# PowerControl.net
KiCad netlist of a schematic drawn in Altium Designer
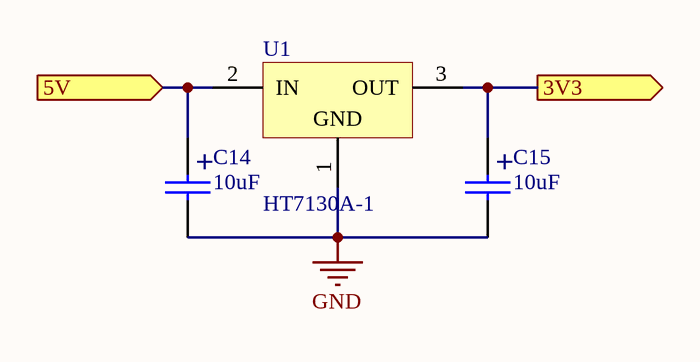
[diagram p0: PowerControl.SchDoc]

(export (version "E")
  (design (tool "Eeschema 10.0.6"))
  (components
    (comp (ref "C14") (value "10uF") (footprint "CAP100RP") (libsource (lib "LIBEBAL") (part "CAPPOL")))
    (comp (ref "C15") (value "10uF") (footprint "CAP100RP") (libsource (lib "LIBEBAL") (part "CAPPOL")))
    (comp (ref "U1")
      (value "HT7130A-1")
      (footprint "BCY-W3/E4")
      (description "3.0V 30mA Low Power,  Low Dropout Voltage (LDO) Regulator")
      (fields (field (name "PUBLISHER") "Altium Limited"))
      (libsource (lib "Holtek Power Mgt Voltage Regulator") (part "HT7130A-1"))
    )
  )
  (nets
    (net (code "1") (name "/3V3") (class "Default")
      (node (ref "C15") (pin "1") (pinfunction "1_1") (pintype "passive"))
      (node (ref "U1") (pin "3") (pinfunction "OUT_3") (pintype "power_in"))
    )
    (net (code "2") (name "/5V") (class "Default")
      (node (ref "C14") (pin "1") (pinfunction "1_1") (pintype "passive"))
      (node (ref "U1") (pin "2") (pinfunction "IN_2") (pintype "power_in"))
    )
    (net (code "3") (name "GND") (class "Default")
      (node (ref "C14") (pin "2") (pinfunction "2_2") (pintype "passive"))
      (node (ref "C15") (pin "2") (pinfunction "2_2") (pintype "passive"))
      (node (ref "U1") (pin "1") (pinfunction "GND_1") (pintype "power_in"))
    )
  )
)
